# POWER.net
KiCad netlist of a schematic drawn in Altium Designer
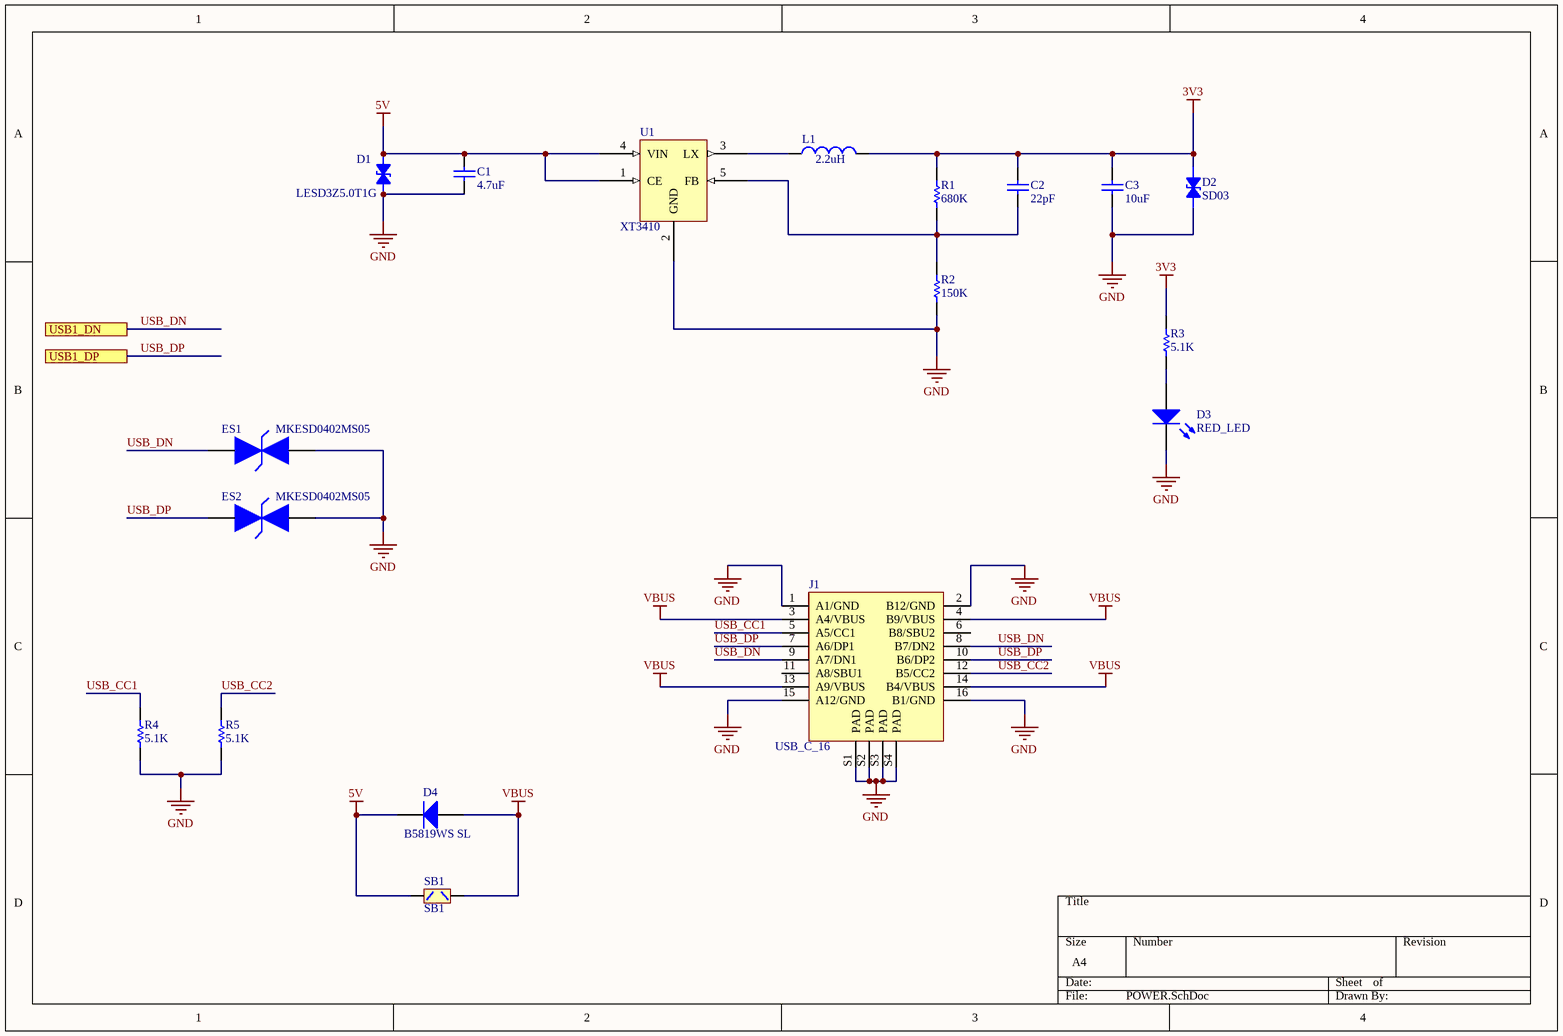
[diagram p0: POWER.SchDoc]

(export (version "E")
  (design (tool "Eeschema 10.0.6"))
  (components
    (comp (ref "C1")
      (value "4.7uF")
      (footprint "0402_Capacitor")
      (description "Capacitor")
      (fields (field (name "PUBLISHER") "Altium Limited"))
      (libsource (lib "Miscellaneous Devices") (part "Cap"))
    )
    (comp (ref "C2")
      (value "22pF")
      (footprint "0402_Capacitor")
      (description "Capacitor")
      (fields (field (name "PUBLISHER") "Altium Limited"))
      (libsource (lib "Miscellaneous Devices") (part "Cap"))
    )
    (comp (ref "C3")
      (value "10uF")
      (footprint "0402_Capacitor")
      (description "Capacitor")
      (fields (field (name "PUBLISHER") "Altium Limited"))
      (libsource (lib "Miscellaneous Devices") (part "Cap"))
    )
    (comp (ref "D1")
      (value "LESD3Z5.0T1G")
      (footprint "SOD-323")
      (libsource (lib "STM32H743") (part "Diode"))
    )
    (comp (ref "D2") (value "SD03") (footprint "SOD-323") (libsource (lib "STM32H743") (part "Diode")))
    (comp (ref "D3")
      (value "RED_LED")
      (footprint "0603_LED_RED")
      (description "Typical INFRARED GaAs LED")
      (fields (field (name "PUBLISHER") "Altium Limited"))
      (libsource (lib "Miscellaneous Devices") (part "LED0"))
    )
    (comp (ref "D4")
      (value "B5819WS SL")
      (footprint "SOD-323")
      (description "Default Diode")
      (fields (field (name "PUBLISHER") "Altium Limited"))
      (libsource (lib "Miscellaneous Devices") (part "Diode"))
    )
    (comp (ref "ES1")
      (value "MKESD0402MS05")
      (footprint "MKESD0402MS05")
      (libsource (lib "2226051_이강민_STM32H743") (part "ESD1"))
    )
    (comp (ref "ES2")
      (value "MKESD0402MS05")
      (footprint "MKESD0402MS05")
      (libsource (lib "2226051_이강민_STM32H743") (part "ESD1"))
    )
    (comp (ref "J1")
      (value "USB_C_16")
      (footprint "USB_C_16PIN_DIP")
      (libsource (lib "2226051_이강민_STM32H743") (part "USB_C_16"))
    )
    (comp (ref "L1")
      (value "2.2uH")
      (footprint "2220(5650)_Inductor")
      (description "Inductor")
      (fields (field (name "PUBLISHER") "Altium Limited"))
      (libsource (lib "Miscellaneous Devices") (part "Inductor"))
    )
    (comp (ref "R1")
      (value "680K")
      (footprint "0402_Resistor")
      (description "Resistor")
      (fields (field (name "Comment") "Res1") (field (name "PUBLISHER") "Altium Limited"))
      (libsource (lib "Miscellaneous Devices") (part "Res1"))
    )
    (comp (ref "R2")
      (value "150K")
      (footprint "0402_Resistor")
      (description "Resistor")
      (fields (field (name "Comment") "Res1") (field (name "PUBLISHER") "Altium Limited"))
      (libsource (lib "Miscellaneous Devices") (part "Res1"))
    )
    (comp (ref "R3")
      (value "5.1K")
      (footprint "0402_Resistor")
      (description "Resistor")
      (fields (field (name "Comment") "Res1") (field (name "PUBLISHER") "Altium Limited"))
      (libsource (lib "Miscellaneous Devices") (part "Res1"))
    )
    (comp (ref "R4")
      (value "5.1K")
      (footprint "0402_Resistor")
      (description "Resistor")
      (fields (field (name "Comment") "Res1") (field (name "PUBLISHER") "Altium Limited"))
      (libsource (lib "Miscellaneous Devices") (part "Res1"))
    )
    (comp (ref "R5")
      (value "5.1K")
      (footprint "0402_Resistor")
      (description "Resistor")
      (fields (field (name "Comment") "Res1") (field (name "PUBLISHER") "Altium Limited"))
      (libsource (lib "Miscellaneous Devices") (part "Res1"))
    )
    (comp (ref "SB1") (value "SB1") (footprint "SB") (libsource (lib "STM32H743") (part "SB1")))
    (comp (ref "U1")
      (value "XT3410")
      (footprint "SOT23_5L")
      (libsource (lib "2226051_이강민_STM32H743") (part "XT3410_My"))
    )
  )
  (nets
    (net (code "1") (name "/USB_CC1") (class "Default")
      (node (ref "J1") (pin "5") (pinfunction "A5/CC1_5") (pintype "passive"))
      (node (ref "R4") (pin "2") (pinfunction "2_2") (pintype "passive"))
    )
    (net (code "2") (name "/USB_CC2") (class "Default")
      (node (ref "J1") (pin "12") (pinfunction "B5/CC2_12") (pintype "passive"))
      (node (ref "R5") (pin "2") (pinfunction "2_2") (pintype "passive"))
    )
    (net (code "3") (name "/USB_DN") (class "Default")
      (node (ref "ES1") (pin "1") (pinfunction "1_1") (pintype "passive"))
      (node (ref "J1") (pin "8") (pinfunction "B7/DN2_8") (pintype "passive"))
      (node (ref "J1") (pin "9") (pinfunction "A7/DN1_9") (pintype "passive"))
    )
    (net (code "4") (name "/USB_DP") (class "Default")
      (node (ref "ES2") (pin "1") (pinfunction "1_1") (pintype "passive"))
      (node (ref "J1") (pin "10") (pinfunction "B6/DP2_10") (pintype "passive"))
      (node (ref "J1") (pin "7") (pinfunction "A6/DP1_7") (pintype "passive"))
    )
    (net (code "5") (name "3V3") (class "Default")
      (node (ref "C2") (pin "2") (pinfunction "2_2") (pintype "passive"))
      (node (ref "C3") (pin "2") (pinfunction "2_2") (pintype "passive"))
      (node (ref "D2") (pin "1") (pinfunction "1_1") (pintype "passive"))
      (node (ref "L1") (pin "2") (pinfunction "2_2") (pintype "passive"))
      (node (ref "R1") (pin "2") (pinfunction "2_2") (pintype "passive"))
      (node (ref "R3") (pin "2") (pinfunction "2_2") (pintype "passive"))
    )
    (net (code "6") (name "5V") (class "Default")
      (node (ref "C1") (pin "2") (pinfunction "2_2") (pintype "passive"))
      (node (ref "D1") (pin "1") (pinfunction "1_1") (pintype "passive"))
      (node (ref "D4") (pin "2") (pinfunction "K_2") (pintype "passive"))
      (node (ref "SB1") (pin "1") (pinfunction "1_1") (pintype "passive"))
      (node (ref "U1") (pin "1") (pinfunction "CE_1") (pintype "input"))
      (node (ref "U1") (pin "4") (pinfunction "VIN_4") (pintype "input"))
    )
    (net (code "7") (name "GND") (class "Default")
      (node (ref "C1") (pin "1") (pinfunction "1_1") (pintype "passive"))
      (node (ref "C3") (pin "1") (pinfunction "1_1") (pintype "passive"))
      (node (ref "D1") (pin "2") (pinfunction "2_2") (pintype "passive"))
      (node (ref "D2") (pin "2") (pinfunction "2_2") (pintype "passive"))
      (node (ref "D3") (pin "2") (pinfunction "K_2") (pintype "passive"))
      (node (ref "ES1") (pin "2") (pinfunction "2_2") (pintype "passive"))
      (node (ref "ES2") (pin "2") (pinfunction "2_2") (pintype "passive"))
      (node (ref "J1") (pin "1") (pinfunction "A1/GND_1") (pintype "passive"))
      (node (ref "J1") (pin "15") (pinfunction "A12/GND_15") (pintype "passive"))
      (node (ref "J1") (pin "16") (pinfunction "B1/GND_16") (pintype "passive"))
      (node (ref "J1") (pin "2") (pinfunction "B12/GND_2") (pintype "passive"))
      (node (ref "J1") (pin "S1") (pinfunction "PAD_S1") (pintype "passive"))
      (node (ref "J1") (pin "S2") (pinfunction "PAD_S2") (pintype "passive"))
      (node (ref "J1") (pin "S3") (pinfunction "PAD_S3") (pintype "passive"))
      (node (ref "J1") (pin "S4") (pinfunction "PAD_S4") (pintype "passive"))
      (node (ref "R2") (pin "1") (pinfunction "1_1") (pintype "passive"))
      (node (ref "R4") (pin "1") (pinfunction "1_1") (pintype "passive"))
      (node (ref "R5") (pin "1") (pinfunction "1_1") (pintype "passive"))
      (node (ref "U1") (pin "2") (pinfunction "GND_2") (pintype "passive"))
    )
    (net (code "8") (name "Net-(D3-A)") (class "Default")
      (node (ref "D3") (pin "1") (pinfunction "A_1") (pintype "passive"))
      (node (ref "R3") (pin "1") (pinfunction "1_1") (pintype "passive"))
    )
    (net (code "9") (name "Net-(U1-FB)") (class "Default")
      (node (ref "C2") (pin "1") (pinfunction "1_1") (pintype "passive"))
      (node (ref "R1") (pin "1") (pinfunction "1_1") (pintype "passive"))
      (node (ref "R2") (pin "2") (pinfunction "2_2") (pintype "passive"))
      (node (ref "U1") (pin "5") (pinfunction "FB_5") (pintype "input"))
    )
    (net (code "10") (name "Net-(U1-LX)") (class "Default")
      (node (ref "L1") (pin "1") (pinfunction "1_1") (pintype "passive"))
      (node (ref "U1") (pin "3") (pinfunction "LX_3") (pintype "output"))
    )
    (net (code "11") (name "VBUS") (class "Default")
      (node (ref "D4") (pin "1") (pinfunction "A_1") (pintype "passive"))
      (node (ref "J1") (pin "13") (pinfunction "A9/VBUS_13") (pintype "passive"))
      (node (ref "J1") (pin "14") (pinfunction "B4/VBUS_14") (pintype "passive"))
      (node (ref "J1") (pin "3") (pinfunction "A4/VBUS_3") (pintype "passive"))
      (node (ref "J1") (pin "4") (pinfunction "B9/VBUS_4") (pintype "passive"))
      (node (ref "SB1") (pin "2") (pinfunction "2_2") (pintype "passive"))
    )
    (net (code "12") (name "unconnected-(J1-A8{slash}SBU1-Pad11)") (class "Default")
      (node (ref "J1") (pin "11") (pinfunction "A8/SBU1_11") (pintype "passive"))
    )
    (net (code "13") (name "unconnected-(J1-B8{slash}SBU2-Pad6)") (class "Default")
      (node (ref "J1") (pin "6") (pinfunction "B8/SBU2_6") (pintype "passive"))
    )
  )
)
